# power.net
KiCad netlist of a schematic drawn in Altium Designer
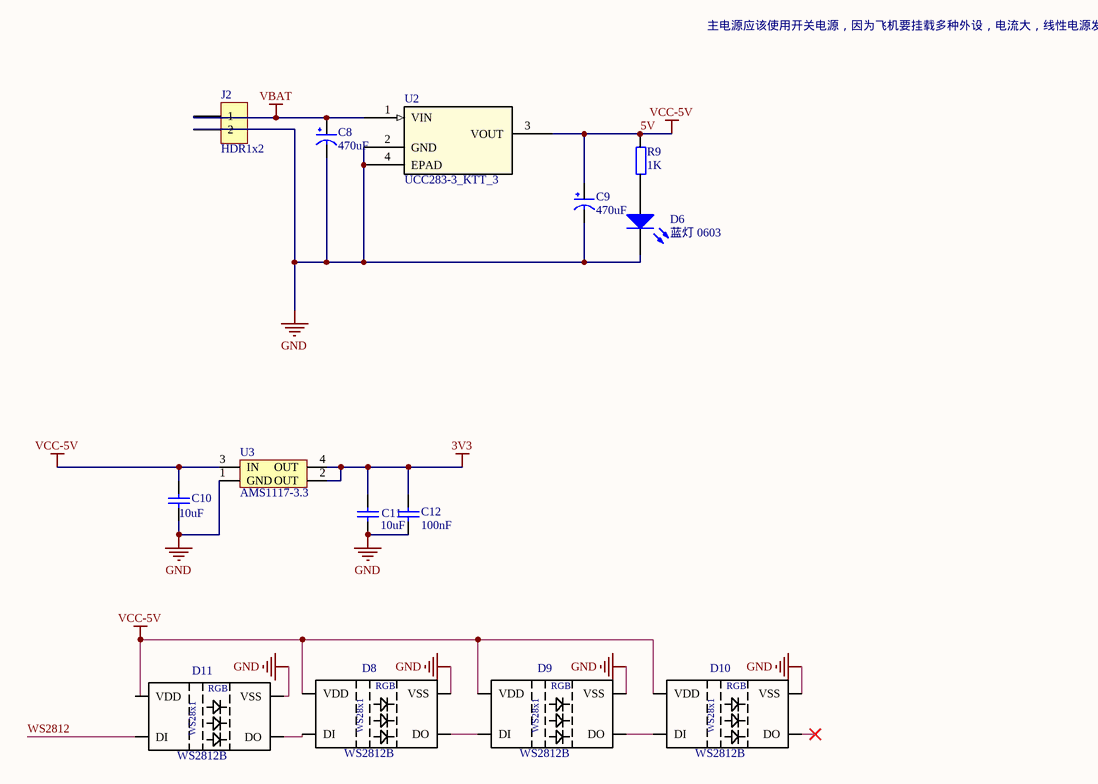
[diagram p0: power.SchDoc]

(export (version "E")
  (design (tool "Eeschema 10.0.6"))
  (components
    (comp (ref "C8") (value "470uF") (footprint "CC6.56.5") (libsource (lib "MyLib") (part "CAP")))
    (comp (ref "C9") (value "470uF") (footprint "CC6.56.5") (libsource (lib "MyLib") (part "CAP")))
    (comp (ref "C10")
      (value "10uF")
      (footprint "0603_C")
      (description "贴片电容")
      (libsource (lib "Miscellaneous Devices LC") (part "0603 10uF (106) 10% 10V"))
    )
    (comp (ref "C11")
      (value "10uF")
      (footprint "0603_C")
      (description "贴片电容")
      (libsource (lib "Miscellaneous Devices LC") (part "0603 10uF (106) 10% 10V"))
    )
    (comp (ref "C12")
      (value "100nF")
      (footprint "0603_C")
      (description "贴片电容")
      (libsource (lib "Miscellaneous Devices LC") (part "0603 100nF (104) 10% 50V"))
    )
    (comp (ref "D6")
      (value "蓝灯 0603")
      (footprint "0603_LED_S1")
      (description "发光二极管")
      (libsource (lib "TM4C123GH6PM") (part "0603 蓝灯"))
    )
    (comp (ref "D8")
      (value "WS2812B")
      (footprint "WS2812B")
      (description "Intelligent Control Led Integrated Light Source Pack Of 10")
      (fields (field (name "MF") "Seeed Technology"))
      (libsource (lib "MyLib") (part "WS2812B"))
    )
    (comp (ref "D9")
      (value "WS2812B")
      (footprint "WS2812B")
      (description "Intelligent Control Led Integrated Light Source Pack Of 10")
      (fields (field (name "MF") "Seeed Technology"))
      (libsource (lib "MyLib") (part "WS2812B"))
    )
    (comp (ref "D10")
      (value "WS2812B")
      (footprint "WS2812B")
      (description "Intelligent Control Led Integrated Light Source Pack Of 10")
      (fields (field (name "MF") "Seeed Technology"))
      (libsource (lib "MyLib") (part "WS2812B"))
    )
    (comp (ref "D11")
      (value "WS2812B")
      (footprint "WS2812B")
      (description "Intelligent Control Led Integrated Light Source Pack Of 10")
      (fields (field (name "MF") "Seeed Technology"))
      (libsource (lib "MyLib") (part "WS2812B"))
    )
    (comp (ref "J2")
      (value "HDR1x2")
      (footprint "Head_Small")
      (description "Connector")
      (libsource (lib "MyLib") (part "HDR1x2"))
    )
    (comp (ref "R9") (value "1K") (footprint "0805_R") (libsource (lib "MyLib") (part "R")))
    (comp (ref "U2")
      (value "UCC283-3_KTT_3")
      (footprint "TO-263-3")
      (description "Imported")
      (fields
        (field (name "MANUFACTURER_PART_NUMBER") "ucc283-3_ktt_3")
        (field (name "GENERIC_PART_NUMBER") "UCC283-3")
      )
      (libsource (lib "MyLib") (part "UCC283-3_KTT_3"))
    )
    (comp (ref "U3")
      (value "AMS1117-3.3")
      (footprint "AMS1117")
      (libsource (lib "阿波罗STM32F4&F7底板封装库") (part "AMS1117"))
    )
  )
  (nets
    (net (code "1") (name "/WS2812") (class "Default")
      (node (ref "D11") (pin "4") (pinfunction "DI_4") (pintype "bidirectional"))
    )
    (net (code "2") (name "3V3") (class "Default")
      (node (ref "C11") (pin "2") (pinfunction "2_2") (pintype "passive"))
      (node (ref "C12") (pin "2") (pinfunction "2_2") (pintype "passive"))
      (node (ref "U3") (pin "2") (pinfunction "OUT_2") (pintype "passive"))
      (node (ref "U3") (pin "4") (pinfunction "OUT_4") (pintype "passive"))
    )
    (net (code "3") (name "GND") (class "Default")
      (node (ref "C10") (pin "1") (pinfunction "1_1") (pintype "passive"))
      (node (ref "C11") (pin "1") (pinfunction "1_1") (pintype "passive"))
      (node (ref "C12") (pin "1") (pinfunction "1_1") (pintype "passive"))
      (node (ref "C8") (pin "2") (pinfunction "GND_2") (pintype "passive"))
      (node (ref "C9") (pin "2") (pinfunction "GND_2") (pintype "passive"))
      (node (ref "D10") (pin "3") (pinfunction "VSS_3") (pintype "bidirectional"))
      (node (ref "D11") (pin "3") (pinfunction "VSS_3") (pintype "bidirectional"))
      (node (ref "D6") (pin "K") (pinfunction "K_K") (pintype "passive"))
      (node (ref "D8") (pin "3") (pinfunction "VSS_3") (pintype "bidirectional"))
      (node (ref "D9") (pin "3") (pinfunction "VSS_3") (pintype "bidirectional"))
      (node (ref "J2") (pin "2") (pinfunction "2_2") (pintype "passive"))
      (node (ref "U2") (pin "2") (pinfunction "GND_2") (pintype "power_in"))
      (node (ref "U2") (pin "4") (pinfunction "EPAD_4") (pintype "passive"))
      (node (ref "U3") (pin "1") (pinfunction "GND_1") (pintype "passive"))
    )
    (net (code "4") (name "Net-(D6-PadA)") (class "Default")
      (node (ref "D6") (pin "A") (pinfunction "A_A") (pintype "passive"))
      (node (ref "R9") (pin "1") (pintype "passive"))
    )
    (net (code "5") (name "Net-(D8-DO)") (class "Default")
      (node (ref "D8") (pin "2") (pinfunction "DO_2") (pintype "bidirectional"))
      (node (ref "D9") (pin "4") (pinfunction "DI_4") (pintype "bidirectional"))
    )
    (net (code "6") (name "Net-(D10-DI)") (class "Default")
      (node (ref "D10") (pin "4") (pinfunction "DI_4") (pintype "bidirectional"))
      (node (ref "D9") (pin "2") (pinfunction "DO_2") (pintype "bidirectional"))
    )
    (net (code "7") (name "Net-(D11-DO)") (class "Default")
      (node (ref "D11") (pin "2") (pinfunction "DO_2") (pintype "bidirectional"))
      (node (ref "D8") (pin "4") (pinfunction "DI_4") (pintype "bidirectional"))
    )
    (net (code "8") (name "VBAT") (class "Default")
      (node (ref "C8") (pin "1") (pinfunction "VCC_1") (pintype "passive"))
      (node (ref "J2") (pin "1") (pinfunction "1_1") (pintype "passive"))
      (node (ref "U2") (pin "1") (pinfunction "VIN_1") (pintype "input"))
    )
    (net (code "9") (name "VCC-5V") (class "Default")
      (node (ref "C10") (pin "2") (pinfunction "2_2") (pintype "passive"))
      (node (ref "C9") (pin "1") (pinfunction "VCC_1") (pintype "passive"))
      (node (ref "D10") (pin "1") (pinfunction "VDD_1") (pintype "bidirectional"))
      (node (ref "D11") (pin "1") (pinfunction "VDD_1") (pintype "bidirectional"))
      (node (ref "D8") (pin "1") (pinfunction "VDD_1") (pintype "bidirectional"))
      (node (ref "D9") (pin "1") (pinfunction "VDD_1") (pintype "bidirectional"))
      (node (ref "R9") (pin "2") (pintype "passive"))
      (node (ref "U2") (pin "3") (pinfunction "VOUT_3") (pintype "passive"))
      (node (ref "U3") (pin "3") (pinfunction "IN_3") (pintype "passive"))
    )
    (net (code "10") (name "unconnected-(D10-DO-Pad2)") (class "Default")
      (node (ref "D10") (pin "2") (pinfunction "DO_2") (pintype "bidirectional+no_connect"))
    )
  )
)
